# Schematic_V6.net
KiCad netlist of a schematic drawn in Altium Designer
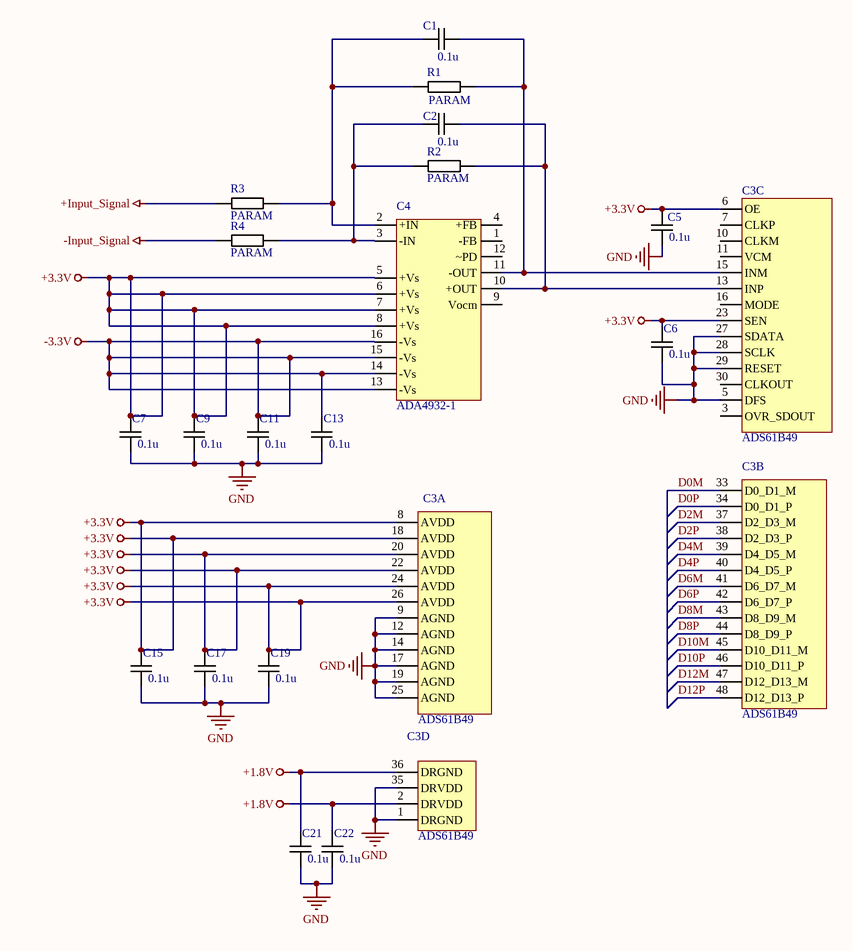
[diagram p0: Schematic_V6.SchDoc]

(export (version "E")
  (design (tool "Eeschema 10.0.6"))
  (components
    (comp (ref "C1")
      (value "0.1u")
      (footprint "Capacitor")
      (libsource (lib "Schematic_Library_V№6") (part "Capacitor"))
    )
    (comp (ref "C2")
      (value "0.1u")
      (footprint "Capacitor")
      (libsource (lib "Schematic_Library_V№6") (part "Capacitor"))
    )
    (comp (ref "C3")
      (value "ADS61B49")
      (footprint "VQFN49")
      (libsource (lib "Schematic_Library_V№6") (part "ADS61B49"))
    )
    (comp (ref "C4")
      (value "ADA4932-1")
      (footprint "PCB_Library_V№6:CP-16-2")
      (libsource (lib "Schematic_Library_V№6") (part "ADA4932-1"))
    )
    (comp (ref "C5")
      (value "0.1u")
      (footprint "Capacitor")
      (libsource (lib "Schematic_Library_V№6") (part "Capacitor"))
    )
    (comp (ref "C6")
      (value "0.1u")
      (footprint "Capacitor")
      (libsource (lib "Schematic_Library_V№6") (part "Capacitor"))
    )
    (comp (ref "C7")
      (value "0.1u")
      (footprint "Capacitor")
      (libsource (lib "Schematic_Library_V№6") (part "Capacitor"))
    )
    (comp (ref "C9")
      (value "0.1u")
      (footprint "Capacitor")
      (libsource (lib "Schematic_Library_V№6") (part "Capacitor"))
    )
    (comp (ref "C11")
      (value "0.1u")
      (footprint "Capacitor")
      (libsource (lib "Schematic_Library_V№6") (part "Capacitor"))
    )
    (comp (ref "C13")
      (value "0.1u")
      (footprint "Capacitor")
      (libsource (lib "Schematic_Library_V№6") (part "Capacitor"))
    )
    (comp (ref "C15")
      (value "0.1u")
      (footprint "Capacitor")
      (libsource (lib "Schematic_Library_V№6") (part "Capacitor"))
    )
    (comp (ref "C17")
      (value "0.1u")
      (footprint "Capacitor")
      (libsource (lib "Schematic_Library_V№6") (part "Capacitor"))
    )
    (comp (ref "C19")
      (value "0.1u")
      (footprint "Capacitor")
      (libsource (lib "Schematic_Library_V№6") (part "Capacitor"))
    )
    (comp (ref "C21")
      (value "0.1u")
      (footprint "Capacitor")
      (libsource (lib "Schematic_Library_V№6") (part "Capacitor"))
    )
    (comp (ref "C22")
      (value "0.1u")
      (footprint "Capacitor")
      (libsource (lib "Schematic_Library_V№6") (part "Capacitor"))
    )
    (comp (ref "R1")
      (value "PARAM")
      (footprint "Resistor")
      (libsource (lib "Schematic_Library_V№6") (part "Resistor"))
    )
    (comp (ref "R2")
      (value "PARAM")
      (footprint "Resistor")
      (libsource (lib "Schematic_Library_V№6") (part "Resistor"))
    )
    (comp (ref "R3")
      (value "PARAM")
      (footprint "Resistor")
      (libsource (lib "Schematic_Library_V№6") (part "Resistor"))
    )
    (comp (ref "R4")
      (value "PARAM")
      (footprint "Resistor")
      (libsource (lib "Schematic_Library_V№6") (part "Resistor"))
    )
  )
  (nets
    (net (code "1") (name "+1.8V") (class "Default")
      (node (ref "C21") (pin "2") (pinfunction "2_2") (pintype "passive"))
      (node (ref "C22") (pin "2") (pinfunction "2_2") (pintype "passive"))
      (node (ref "C3") (pin "2") (pinfunction "DRVDD_2") (pintype "passive"))
      (node (ref "C3") (pin "36") (pinfunction "DRGND_36") (pintype "passive"))
    )
    (net (code "2") (name "+3.3V") (class "Default")
      (node (ref "C15") (pin "2") (pinfunction "2_2") (pintype "passive"))
      (node (ref "C17") (pin "2") (pinfunction "2_2") (pintype "passive"))
      (node (ref "C19") (pin "2") (pinfunction "2_2") (pintype "passive"))
      (node (ref "C3") (pin "18") (pinfunction "AVDD_18") (pintype "passive"))
      (node (ref "C3") (pin "20") (pinfunction "AVDD_20") (pintype "passive"))
      (node (ref "C3") (pin "22") (pinfunction "AVDD_22") (pintype "passive"))
      (node (ref "C3") (pin "23") (pinfunction "SEN_23") (pintype "passive"))
      (node (ref "C3") (pin "24") (pinfunction "AVDD_24") (pintype "passive"))
      (node (ref "C3") (pin "26") (pinfunction "AVDD_26") (pintype "passive"))
      (node (ref "C3") (pin "6") (pinfunction "OE_6") (pintype "passive"))
      (node (ref "C3") (pin "8") (pinfunction "AVDD_8") (pintype "passive"))
      (node (ref "C4") (pin "5") (pinfunction "+Vs_5") (pintype "passive"))
      (node (ref "C4") (pin "6") (pinfunction "+Vs_6") (pintype "passive"))
      (node (ref "C4") (pin "7") (pinfunction "+Vs_7") (pintype "passive"))
      (node (ref "C4") (pin "8") (pinfunction "+Vs_8") (pintype "passive"))
      (node (ref "C5") (pin "2") (pinfunction "2_2") (pintype "passive"))
      (node (ref "C6") (pin "2") (pinfunction "2_2") (pintype "passive"))
      (node (ref "C7") (pin "2") (pinfunction "2_2") (pintype "passive"))
      (node (ref "C9") (pin "2") (pinfunction "2_2") (pintype "passive"))
    )
    (net (code "3") (name "+Input_Signal") (class "Default")
      (node (ref "R3") (pin "1") (pinfunction "1_1") (pintype "passive"))
    )
    (net (code "4") (name "-3.3V") (class "Default")
      (node (ref "C11") (pin "2") (pinfunction "2_2") (pintype "passive"))
      (node (ref "C13") (pin "2") (pinfunction "2_2") (pintype "passive"))
      (node (ref "C4") (pin "13") (pinfunction "-Vs_13") (pintype "passive"))
      (node (ref "C4") (pin "14") (pinfunction "-Vs_14") (pintype "passive"))
      (node (ref "C4") (pin "15") (pinfunction "-Vs_15") (pintype "passive"))
      (node (ref "C4") (pin "16") (pinfunction "-Vs_16") (pintype "passive"))
    )
    (net (code "5") (name "-Input_Signal") (class "Default")
      (node (ref "R4") (pin "1") (pinfunction "1_1") (pintype "passive"))
    )
    (net (code "6") (name "/D0M") (class "Default")
      (node (ref "C3") (pin "33") (pinfunction "D0_D1_M_33") (pintype "passive"))
    )
    (net (code "7") (name "/D0P") (class "Default")
      (node (ref "C3") (pin "34") (pinfunction "D0_D1_P_34") (pintype "passive"))
    )
    (net (code "8") (name "/D2M") (class "Default")
      (node (ref "C3") (pin "37") (pinfunction "D2_D3_M_37") (pintype "passive"))
    )
    (net (code "9") (name "/D2P") (class "Default")
      (node (ref "C3") (pin "38") (pinfunction "D2_D3_P_38") (pintype "passive"))
    )
    (net (code "10") (name "/D4M") (class "Default")
      (node (ref "C3") (pin "39") (pinfunction "D4_D5_M_39") (pintype "passive"))
    )
    (net (code "11") (name "/D4P") (class "Default")
      (node (ref "C3") (pin "40") (pinfunction "D4_D5_P_40") (pintype "passive"))
    )
    (net (code "12") (name "/D6M") (class "Default")
      (node (ref "C3") (pin "41") (pinfunction "D6_D7_M_41") (pintype "passive"))
    )
    (net (code "13") (name "/D6P") (class "Default")
      (node (ref "C3") (pin "42") (pinfunction "D6_D7_P_42") (pintype "passive"))
    )
    (net (code "14") (name "/D8M") (class "Default")
      (node (ref "C3") (pin "43") (pinfunction "D8_D9_M_43") (pintype "passive"))
    )
    (net (code "15") (name "/D8P") (class "Default")
      (node (ref "C3") (pin "44") (pinfunction "D8_D9_P_44") (pintype "passive"))
    )
    (net (code "16") (name "/D10M") (class "Default")
      (node (ref "C3") (pin "45") (pinfunction "D10_D11_M_45") (pintype "passive"))
    )
    (net (code "17") (name "/D10P") (class "Default")
      (node (ref "C3") (pin "46") (pinfunction "D10_D11_P_46") (pintype "passive"))
    )
    (net (code "18") (name "/D12M") (class "Default")
      (node (ref "C3") (pin "47") (pinfunction "D12_D13_M_47") (pintype "passive"))
    )
    (net (code "19") (name "/D12P") (class "Default")
      (node (ref "C3") (pin "48") (pinfunction "D12_D13_P_48") (pintype "passive"))
    )
    (net (code "20") (name "GND") (class "Default")
      (node (ref "C11") (pin "1") (pinfunction "1_1") (pintype "passive"))
      (node (ref "C13") (pin "1") (pinfunction "1_1") (pintype "passive"))
      (node (ref "C15") (pin "1") (pinfunction "1_1") (pintype "passive"))
      (node (ref "C17") (pin "1") (pinfunction "1_1") (pintype "passive"))
      (node (ref "C19") (pin "1") (pinfunction "1_1") (pintype "passive"))
      (node (ref "C21") (pin "1") (pinfunction "1_1") (pintype "passive"))
      (node (ref "C22") (pin "1") (pinfunction "1_1") (pintype "passive"))
      (node (ref "C3") (pin "1") (pinfunction "DRGND_1") (pintype "passive"))
      (node (ref "C3") (pin "12") (pinfunction "AGND_12") (pintype "passive"))
      (node (ref "C3") (pin "14") (pinfunction "AGND_14") (pintype "passive"))
      (node (ref "C3") (pin "17") (pinfunction "AGND_17") (pintype "passive"))
      (node (ref "C3") (pin "19") (pinfunction "AGND_19") (pintype "passive"))
      (node (ref "C3") (pin "25") (pinfunction "AGND_25") (pintype "passive"))
      (node (ref "C3") (pin "27") (pinfunction "SDATA_27") (pintype "passive"))
      (node (ref "C3") (pin "28") (pinfunction "SCLK_28") (pintype "passive"))
      (node (ref "C3") (pin "29") (pinfunction "RESET_29") (pintype "passive"))
      (node (ref "C3") (pin "35") (pinfunction "DRVDD_35") (pintype "passive"))
      (node (ref "C3") (pin "5") (pinfunction "DFS_5") (pintype "passive"))
      (node (ref "C3") (pin "9") (pinfunction "AGND_9") (pintype "passive"))
      (node (ref "C5") (pin "1") (pinfunction "1_1") (pintype "passive"))
      (node (ref "C6") (pin "1") (pinfunction "1_1") (pintype "passive"))
      (node (ref "C7") (pin "1") (pinfunction "1_1") (pintype "passive"))
      (node (ref "C9") (pin "1") (pinfunction "1_1") (pintype "passive"))
    )
    (net (code "21") (name "Net-(C3C-INM)") (class "Default")
      (node (ref "C1") (pin "1") (pinfunction "1_1") (pintype "passive"))
      (node (ref "C3") (pin "15") (pinfunction "INM_15") (pintype "passive"))
      (node (ref "C4") (pin "11") (pinfunction "-OUT_11") (pintype "passive"))
      (node (ref "R1") (pin "2") (pinfunction "2_2") (pintype "passive"))
    )
    (net (code "22") (name "Net-(C3C-INP)") (class "Default")
      (node (ref "C2") (pin "2") (pinfunction "2_2") (pintype "passive"))
      (node (ref "C3") (pin "13") (pinfunction "INP_13") (pintype "passive"))
      (node (ref "C4") (pin "10") (pinfunction "+OUT_10") (pintype "passive"))
      (node (ref "R2") (pin "2") (pinfunction "2_2") (pintype "passive"))
    )
    (net (code "23") (name "Net-(C4-+IN)") (class "Default")
      (node (ref "C1") (pin "2") (pinfunction "2_2") (pintype "passive"))
      (node (ref "C4") (pin "2") (pinfunction "+IN_2") (pintype "passive"))
      (node (ref "R1") (pin "1") (pinfunction "1_1") (pintype "passive"))
      (node (ref "R3") (pin "2") (pinfunction "2_2") (pintype "passive"))
    )
    (net (code "24") (name "Net-(C4--IN)") (class "Default")
      (node (ref "C2") (pin "1") (pinfunction "1_1") (pintype "passive"))
      (node (ref "C4") (pin "3") (pinfunction "-IN_3") (pintype "passive"))
      (node (ref "R2") (pin "1") (pinfunction "1_1") (pintype "passive"))
      (node (ref "R4") (pin "2") (pinfunction "2_2") (pintype "passive"))
    )
    (net (code "25") (name "unconnected-(C3C-CLKM-Pad10)") (class "Default")
      (node (ref "C3") (pin "10") (pinfunction "CLKM_10") (pintype "passive"))
    )
    (net (code "26") (name "unconnected-(C3C-CLKOUT-Pad30)") (class "Default")
      (node (ref "C3") (pin "30") (pinfunction "CLKOUT_30") (pintype "passive"))
    )
    (net (code "27") (name "unconnected-(C3C-CLKP-Pad7)") (class "Default")
      (node (ref "C3") (pin "7") (pinfunction "CLKP_7") (pintype "passive"))
    )
    (net (code "28") (name "unconnected-(C3C-MODE-Pad16)") (class "Default")
      (node (ref "C3") (pin "16") (pinfunction "MODE_16") (pintype "passive"))
    )
    (net (code "29") (name "unconnected-(C3C-OVR_SDOUT-Pad3)") (class "Default")
      (node (ref "C3") (pin "3") (pinfunction "OVR_SDOUT_3") (pintype "passive"))
    )
    (net (code "30") (name "unconnected-(C3C-VCM-Pad11)") (class "Default")
      (node (ref "C3") (pin "11") (pinfunction "VCM_11") (pintype "passive"))
    )
    (net (code "31") (name "unconnected-(C4-+FB-Pad4)") (class "Default")
      (node (ref "C4") (pin "4") (pinfunction "+FB_4") (pintype "passive"))
    )
    (net (code "32") (name "unconnected-(C4--FB-Pad1)") (class "Default")
      (node (ref "C4") (pin "1") (pinfunction "-FB_1") (pintype "passive"))
    )
    (net (code "33") (name "unconnected-(C4-Vocm-Pad9)") (class "Default")
      (node (ref "C4") (pin "9") (pinfunction "Vocm_9") (pintype "passive"))
    )
    (net (code "34") (name "unconnected-(C4-~PD-Pad12)") (class "Default")
      (node (ref "C4") (pin "12") (pinfunction "~PD_12") (pintype "passive"))
    )
  )
)
